# design.net
KiCad netlist of a schematic drawn in Altium Designer
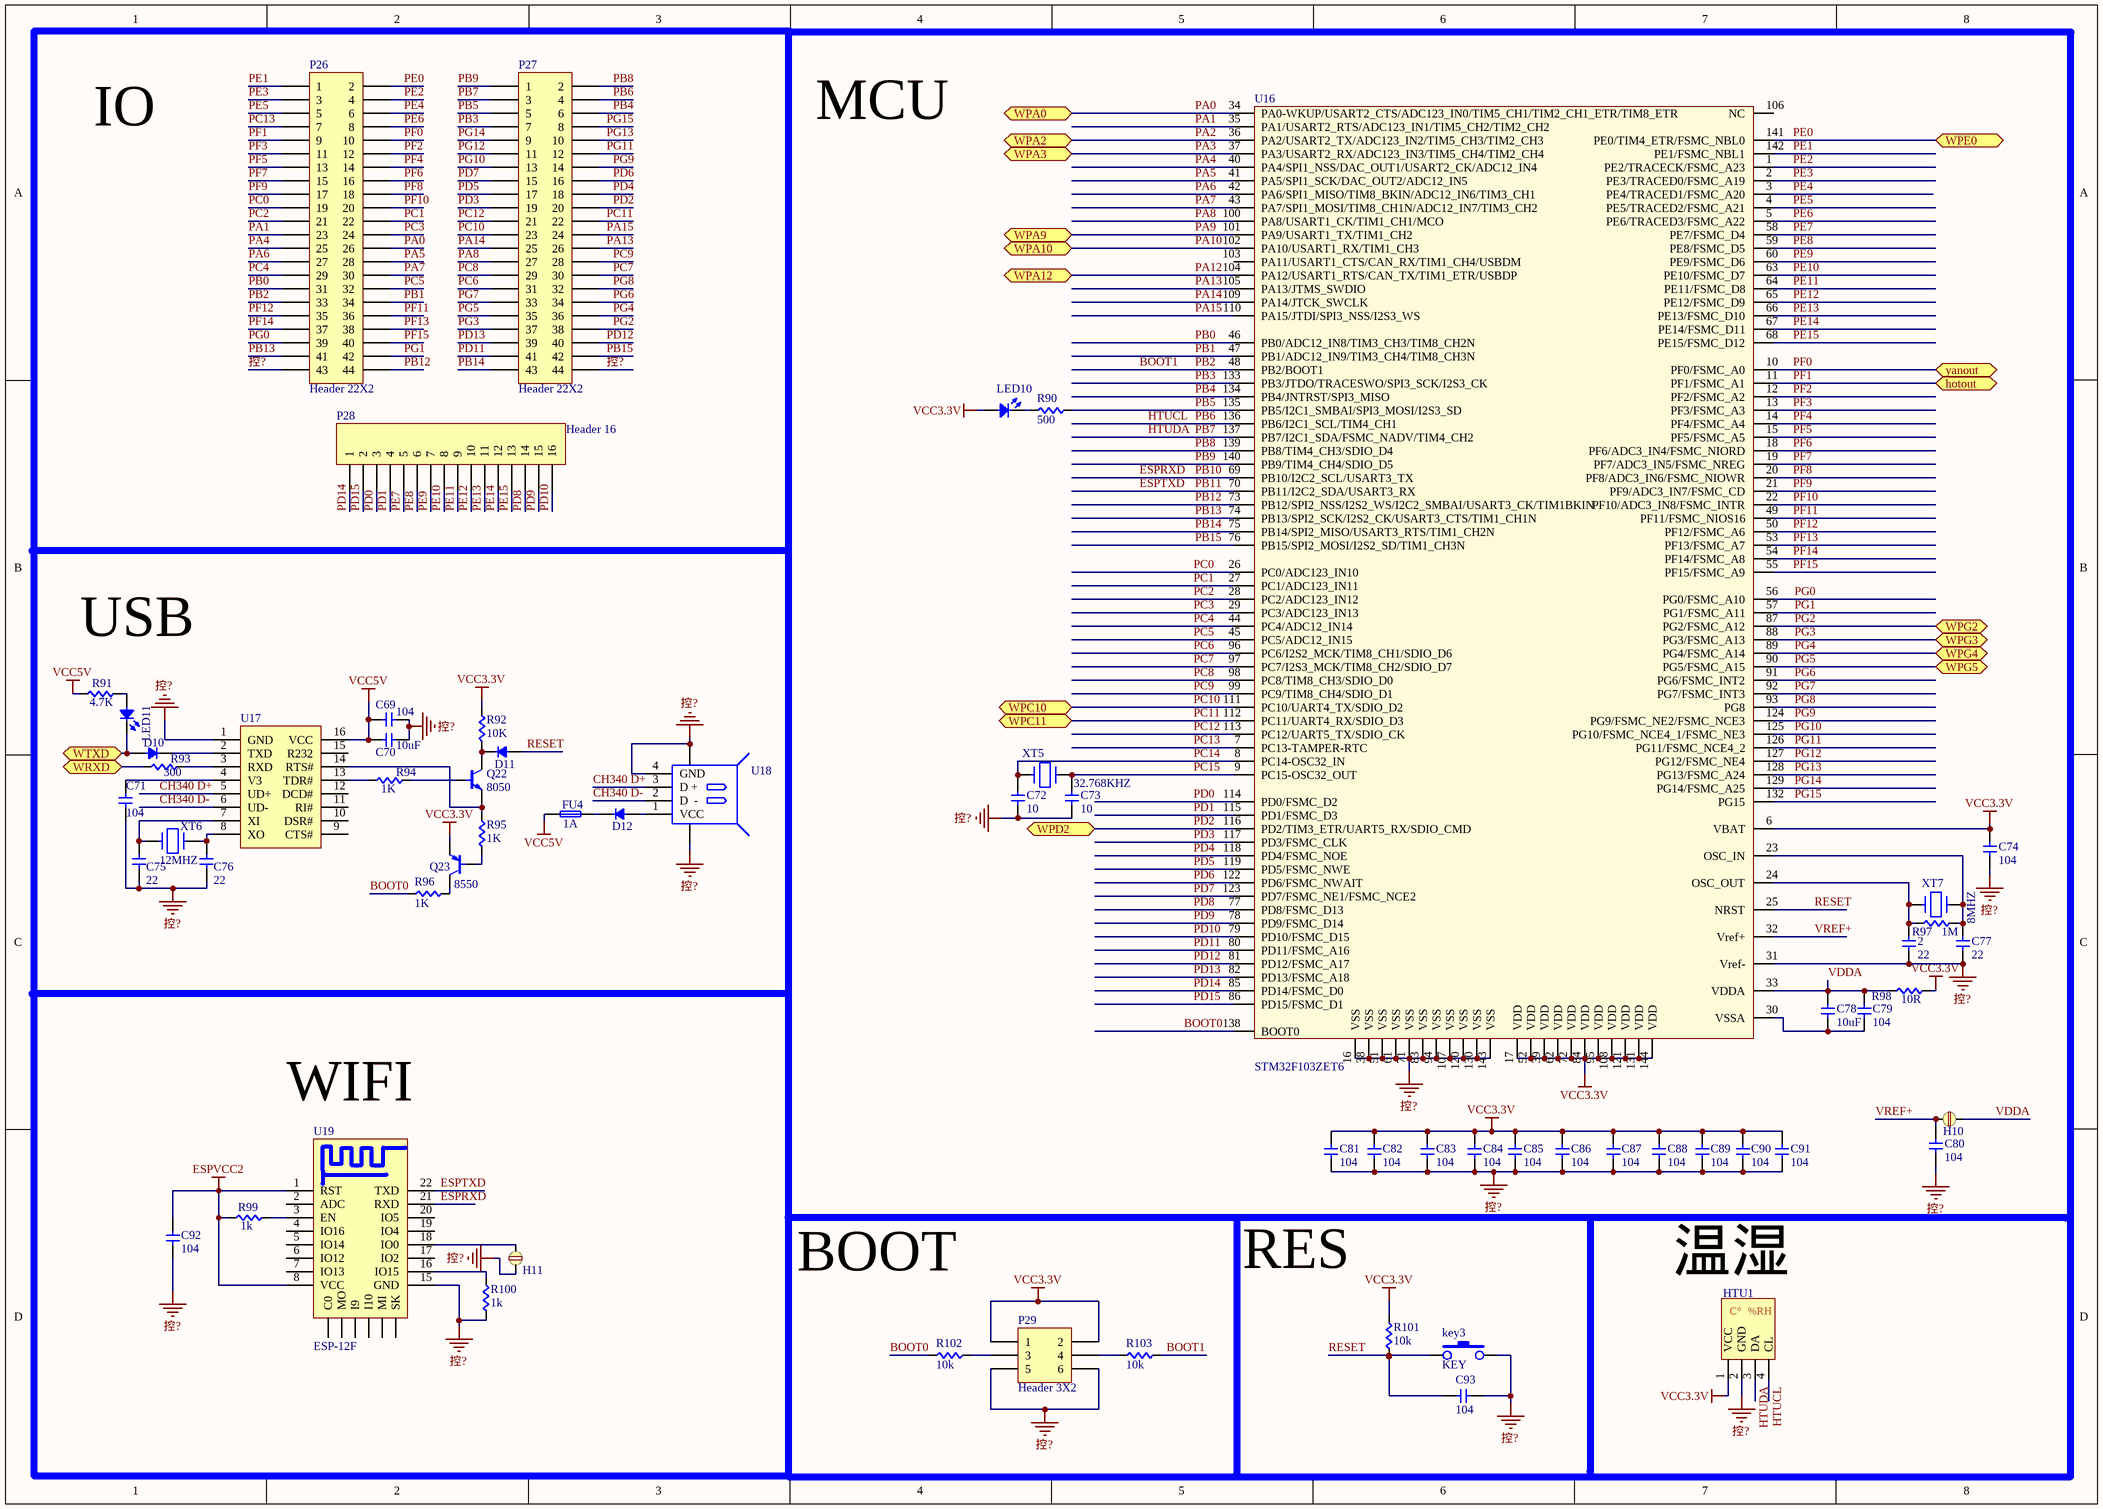
[diagram p0: 小车主板原理图.SchDoc]

(export (version "E")
  (design (tool "Eeschema 10.0.6"))
  (components
    (comp (ref "2") (value "22") (footprint "0805C") (libsource (lib "史福祥库") (part "C")))
    (comp (ref "C69") (value "104") (footprint "0805C") (libsource (lib "史福祥库") (part "C")))
    (comp (ref "C70") (value "10uF") (footprint "0805C") (libsource (lib "史福祥库") (part "C")))
    (comp (ref "C71") (value "104") (footprint "0805C") (libsource (lib "史福祥库") (part "C")))
    (comp (ref "C72") (value "10") (footprint "0805C") (libsource (lib "史福祥库") (part "C")))
    (comp (ref "C73") (value "10") (footprint "0805C") (libsource (lib "史福祥库") (part "C")))
    (comp (ref "C74") (value "104") (footprint "0805C") (libsource (lib "史福祥库") (part "C")))
    (comp (ref "C75") (value "22") (footprint "0805C") (libsource (lib "史福祥库") (part "C")))
    (comp (ref "C76") (value "22") (footprint "0805C") (libsource (lib "史福祥库") (part "C")))
    (comp (ref "C77") (value "22") (footprint "0805C") (libsource (lib "史福祥库") (part "C")))
    (comp (ref "C78") (value "10uF") (footprint "0805C") (libsource (lib "史福祥库") (part "C")))
    (comp (ref "C79") (value "104") (footprint "0805C") (libsource (lib "史福祥库") (part "C")))
    (comp (ref "C80") (value "104") (footprint "0805C") (libsource (lib "史福祥库") (part "C")))
    (comp (ref "C81") (value "104") (footprint "0805C") (libsource (lib "史福祥库") (part "C")))
    (comp (ref "C82") (value "104") (footprint "0805C") (libsource (lib "史福祥库") (part "C")))
    (comp (ref "C83") (value "104") (footprint "0805C") (libsource (lib "史福祥库") (part "C")))
    (comp (ref "C84") (value "104") (footprint "0805C") (libsource (lib "史福祥库") (part "C")))
    (comp (ref "C85") (value "104") (footprint "0805C") (libsource (lib "史福祥库") (part "C")))
    (comp (ref "C86") (value "104") (footprint "0805C") (libsource (lib "史福祥库") (part "C")))
    (comp (ref "C87") (value "104") (footprint "0805C") (libsource (lib "史福祥库") (part "C")))
    (comp (ref "C88") (value "104") (footprint "0805C") (libsource (lib "史福祥库") (part "C")))
    (comp (ref "C89") (value "104") (footprint "0805C") (libsource (lib "史福祥库") (part "C")))
    (comp (ref "C90") (value "104") (footprint "0805C") (libsource (lib "史福祥库") (part "C")))
    (comp (ref "C91") (value "104") (footprint "0805C") (libsource (lib "史福祥库") (part "C")))
    (comp (ref "C92") (value "104") (footprint "0805C") (libsource (lib "史福祥库") (part "C")))
    (comp (ref "C93") (value "104") (footprint "0805C") (libsource (lib "史福祥库") (part "C")))
    (comp (ref "D10")
      (value "D")
      (footprint "1206D")
      (fields (field (name "PUBLISHER") "Altium Limited"))
      (libsource (lib "史福祥库") (part "D"))
    )
    (comp (ref "D11")
      (value "D")
      (footprint "1206D")
      (fields (field (name "PUBLISHER") "Altium Limited"))
      (libsource (lib "史福祥库") (part "D"))
    )
    (comp (ref "D12")
      (value "D")
      (footprint "DO-214-M7-  4007贴片")
      (fields (field (name "PUBLISHER") "Altium Limited"))
      (libsource (lib "史福祥库") (part "D"))
    )
    (comp (ref "FU4") (value "1A") (footprint "1206") (libsource (lib "史福祥库") (part "FUSE")))
    (comp (ref "H10") (value "2脚") (footprint "2P") (libsource (lib "") (part "2脚_1")))
    (comp (ref "H11") (value "2脚") (footprint "2P") (libsource (lib "史福祥库") (part "2脚")))
    (comp (ref "HTU1") (value "HTU21D") (footprint "HDR1X4H") (libsource (lib "史福祥库") (part "HTU21D")))
    (comp (ref "key3") (value "KEY") (footprint "AN12") (libsource (lib "史福祥库") (part "KEY")))
    (comp (ref "LED10")
      (value "LED")
      (footprint "0805D")
      (fields (field (name "PUBLISHER") "Altium Limited"))
      (libsource (lib "史福祥库") (part "LED"))
    )
    (comp (ref "LED11")
      (value "LED")
      (footprint "0805D")
      (fields (field (name "PUBLISHER") "Altium Limited"))
      (libsource (lib "史福祥库") (part "LED"))
    )
    (comp (ref "P26")
      (value "Header 22X2")
      (footprint "HDR2X22")
      (description "Header, 22-Pin, Dual row")
      (fields (field (name "PUBLISHER") "Altium Limited"))
      (libsource (lib "Miscellaneous Connectors") (part "Header 22X2"))
    )
    (comp (ref "P27")
      (value "Header 22X2")
      (footprint "HDR2X22")
      (description "Header, 22-Pin, Dual row")
      (fields (field (name "PUBLISHER") "Altium Limited"))
      (libsource (lib "Miscellaneous Connectors") (part "Header 22X2"))
    )
    (comp (ref "P28")
      (value "Header 16")
      (footprint "HDR1X16")
      (description "Header, 16-Pin")
      (fields (field (name "PUBLISHER") "Altium Limited"))
      (libsource (lib "Miscellaneous Connectors") (part "Header 16"))
    )
    (comp (ref "P29")
      (value "Header 3X2")
      (footprint "HDR2X3")
      (description "Header, 3-Pin, Dual row")
      (fields (field (name "PUBLISHER") "Altium Limited"))
      (libsource (lib "Miscellaneous Connectors") (part "Header 3X2"))
    )
    (comp (ref "Q22") (value "8050") (footprint "SOT-23") (libsource (lib "史福祥库") (part "NPN")))
    (comp (ref "Q23") (value "8550") (footprint "SOT-23") (libsource (lib "史福祥库") (part "PNP")))
    (comp (ref "R90") (value "500") (footprint "0805") (libsource (lib "史福祥库") (part "Res")))
    (comp (ref "R91") (value "4.7K") (footprint "0805") (libsource (lib "史福祥库") (part "Res")))
    (comp (ref "R92") (value "10K") (footprint "0805") (libsource (lib "史福祥库") (part "Res")))
    (comp (ref "R93") (value "300") (footprint "0805") (libsource (lib "史福祥库") (part "Res")))
    (comp (ref "R94") (value "1K") (footprint "0805") (libsource (lib "史福祥库") (part "Res")))
    (comp (ref "R95") (value "1K") (footprint "0805") (libsource (lib "史福祥库") (part "Res")))
    (comp (ref "R96") (value "1K") (footprint "0805") (libsource (lib "史福祥库") (part "Res")))
    (comp (ref "R97") (value "1M") (footprint "0805") (libsource (lib "史福祥库") (part "Res")))
    (comp (ref "R98") (value "10R") (footprint "0805") (libsource (lib "史福祥库") (part "Res")))
    (comp (ref "R99") (value "1k") (footprint "0805") (libsource (lib "史福祥库") (part "Res")))
    (comp (ref "R100") (value "1k") (footprint "0805") (libsource (lib "史福祥库") (part "Res")))
    (comp (ref "R101") (value "10k") (footprint "0805") (libsource (lib "史福祥库") (part "Res")))
    (comp (ref "R102") (value "10k") (footprint "0805") (libsource (lib "史福祥库") (part "Res")))
    (comp (ref "R103") (value "10k") (footprint "0805") (libsource (lib "史福祥库") (part "Res")))
    (comp (ref "U16")
      (value "STM32F103ZET6")
      (footprint "TQFP144")
      (libsource (lib "史福祥库") (part "STM32F103ZET6"))
    )
    (comp (ref "U17") (value "CH340G") (footprint "SOP-16") (libsource (lib "史福祥库") (part "CH340G")))
    (comp (ref "U18") (value "USB A") (footprint "USB A 公") (libsource (lib "史福祥库") (part "USB A")))
    (comp (ref "U19") (value "ESP-12F") (footprint "ESP-12F") (libsource (lib "史福祥库") (part "ESP-12F")))
    (comp (ref "XT5") (value "32.768KHZ") (footprint "XTAL-T") (libsource (lib "史福祥库") (part "XTAL")))
    (comp (ref "XT6") (value "12MHZ") (footprint "XTAL-T") (libsource (lib "史福祥库") (part "XTAL")))
    (comp (ref "XT7") (value "8MHZ") (footprint "XTAL-T") (libsource (lib "史福祥库") (part "XTAL")))
  )
  (nets
    (net (code "1") (name "/BOOT0") (class "Default")
      (node (ref "R102") (pin "2") (pinfunction "2_2") (pintype "passive"))
      (node (ref "R96") (pin "1") (pinfunction "1_1") (pintype "passive"))
      (node (ref "U16") (pin "138") (pinfunction "BOOT0_138") (pintype "passive"))
    )
    (net (code "2") (name "/BOOT1") (class "Default")
      (node (ref "P26") (pin "33") (pinfunction "33_33") (pintype "passive"))
      (node (ref "R103") (pin "1") (pinfunction "1_1") (pintype "passive"))
      (node (ref "U16") (pin "48") (pinfunction "PB2/BOOT1_48") (pintype "passive"))
    )
    (net (code "3") (name "/CH340 D+") (class "Default")
      (node (ref "U17") (pin "5") (pinfunction "UD+_5") (pintype "passive"))
      (node (ref "U18") (pin "3") (pinfunction "D_+_3") (pintype "passive"))
    )
    (net (code "4") (name "/CH340 D-") (class "Default")
      (node (ref "U17") (pin "6") (pinfunction "UD-_6") (pintype "passive"))
      (node (ref "U18") (pin "2") (pinfunction "D__-_2") (pintype "passive"))
    )
    (net (code "5") (name "/ESPRXD") (class "Default")
      (node (ref "U16") (pin "69") (pinfunction "PB10/I2C2_SCL/USART3_TX_69") (pintype "passive"))
      (node (ref "U19") (pin "21") (pinfunction "RXD_21") (pintype "passive"))
    )
    (net (code "6") (name "/ESPTXD") (class "Default")
      (node (ref "U16") (pin "70") (pinfunction "PB11/I2C2_SDA/USART3_RX_70") (pintype "passive"))
      (node (ref "U19") (pin "22") (pinfunction "TXD_22") (pintype "passive"))
    )
    (net (code "7") (name "/HTUCL") (class "Default")
      (node (ref "HTU1") (pin "4") (pinfunction "CL_4") (pintype "tri_state"))
      (node (ref "P27") (pin "4") (pinfunction "4_4") (pintype "passive"))
      (node (ref "U16") (pin "136") (pinfunction "PB6/I2C1_SCL/TIM4_CH1_136") (pintype "passive"))
    )
    (net (code "8") (name "/HTUDA") (class "Default")
      (node (ref "HTU1") (pin "3") (pinfunction "DA_3") (pintype "tri_state"))
      (node (ref "P27") (pin "3") (pinfunction "3_3") (pintype "passive"))
      (node (ref "U16") (pin "137") (pinfunction "PB7/I2C1_SDA/FSMC_NADV/TIM4_CH2_137") (pintype "passive"))
    )
    (net (code "9") (name "/PA0") (class "Default")
      (node (ref "P26") (pin "26") (pinfunction "26_26") (pintype "passive"))
      (node (ref "U16") (pin "34") (pinfunction "PA0-WKUP/USART2_CTS/ADC123_IN0/TIM5_CH1/TIM2_CH1_ETR/TIM8_ETR_34") (pintype "passive"))
    )
    (net (code "10") (name "/PA1") (class "Default")
      (node (ref "P26") (pin "23") (pinfunction "23_23") (pintype "passive"))
      (node (ref "U16") (pin "35") (pinfunction "PA1/USART2_RTS/ADC123_IN1/TIM5_CH2/TIM2_CH2_35") (pintype "passive"))
    )
    (net (code "11") (name "/PA2") (class "Default")
      (node (ref "U16") (pin "36") (pinfunction "PA2/USART2_TX/ADC123_IN2/TIM5_CH3/TIM2_CH3_36") (pintype "passive"))
    )
    (net (code "12") (name "/PA3") (class "Default")
      (node (ref "U16") (pin "37") (pinfunction "PA3/USART2_RX/ADC123_IN3/TIM5_CH4/TIM2_CH4_37") (pintype "passive"))
    )
    (net (code "13") (name "/PA4") (class "Default")
      (node (ref "P26") (pin "25") (pinfunction "25_25") (pintype "passive"))
      (node (ref "U16") (pin "40") (pinfunction "PA4/SPI1_NSS/DAC_OUT1/USART2_CK/ADC12_IN4_40") (pintype "passive"))
    )
    (net (code "14") (name "/PA5") (class "Default")
      (node (ref "P26") (pin "28") (pinfunction "28_28") (pintype "passive"))
      (node (ref "U16") (pin "41") (pinfunction "PA5/SPI1_SCK/DAC_OUT2/ADC12_IN5_41") (pintype "passive"))
    )
    (net (code "15") (name "/PA6") (class "Default")
      (node (ref "P26") (pin "27") (pinfunction "27_27") (pintype "passive"))
      (node (ref "U16") (pin "42") (pinfunction "PA6/SPI1_MISO/TIM8_BKIN/ADC12_IN6/TIM3_CH1_42") (pintype "passive"))
    )
    (net (code "16") (name "/PA7") (class "Default")
      (node (ref "P26") (pin "30") (pinfunction "30_30") (pintype "passive"))
      (node (ref "U16") (pin "43") (pinfunction "PA7/SPI1_MOSI/TIM8_CH1N/ADC12_IN7/TIM3_CH2_43") (pintype "passive"))
    )
    (net (code "17") (name "/PA8") (class "Default")
      (node (ref "P27") (pin "27") (pinfunction "27_27") (pintype "passive"))
      (node (ref "U16") (pin "100") (pinfunction "PA8/USART1_CK/TIM1_CH1/MCO_100") (pintype "passive"))
    )
    (net (code "18") (name "/PA9") (class "Default")
      (node (ref "U16") (pin "101") (pinfunction "PA9/USART1_TX/TIM1_CH2_101") (pintype "passive"))
    )
    (net (code "19") (name "/PA10") (class "Default")
      (node (ref "U16") (pin "102") (pinfunction "PA10/USART1_RX/TIM1_CH3_102") (pintype "passive"))
    )
    (net (code "20") (name "/PA12") (class "Default")
      (node (ref "U16") (pin "104") (pinfunction "PA12/USART1_RTS/CAN_TX/TIM1_ETR/USBDP_104") (pintype "passive"))
    )
    (net (code "21") (name "/PA13") (class "Default")
      (node (ref "P27") (pin "26") (pinfunction "26_26") (pintype "passive"))
      (node (ref "U16") (pin "105") (pinfunction "PA13/JTMS_SWDIO_105") (pintype "passive"))
    )
    (net (code "22") (name "/PA14") (class "Default")
      (node (ref "P27") (pin "25") (pinfunction "25_25") (pintype "passive"))
      (node (ref "U16") (pin "109") (pinfunction "PA14/JTCK_SWCLK_109") (pintype "passive"))
    )
    (net (code "23") (name "/PA15") (class "Default")
      (node (ref "P27") (pin "24") (pinfunction "24_24") (pintype "passive"))
      (node (ref "U16") (pin "110") (pinfunction "PA15/JTDI/SPI3_NSS/I2S3_WS_110") (pintype "passive"))
    )
    (net (code "24") (name "/PB0") (class "Default")
      (node (ref "P26") (pin "31") (pinfunction "31_31") (pintype "passive"))
      (node (ref "U16") (pin "46") (pinfunction "PB0/ADC12_IN8/TIM3_CH3/TIM8_CH2N_46") (pintype "passive"))
    )
    (net (code "25") (name "/PB1") (class "Default")
      (node (ref "P26") (pin "34") (pinfunction "34_34") (pintype "passive"))
      (node (ref "U16") (pin "47") (pinfunction "PB1/ADC12_IN9/TIM3_CH4/TIM8_CH3N_47") (pintype "passive"))
    )
    (net (code "26") (name "/PB3") (class "Default")
      (node (ref "P27") (pin "7") (pinfunction "7_7") (pintype "passive"))
      (node (ref "U16") (pin "133") (pinfunction "PB3/JTDO/TRACESWO/SPI3_SCK/I2S3_CK_133") (pintype "passive"))
    )
    (net (code "27") (name "/PB4") (class "Default")
      (node (ref "P27") (pin "6") (pinfunction "6_6") (pintype "passive"))
      (node (ref "U16") (pin "134") (pinfunction "PB4/JNTRST/SPI3_MISO_134") (pintype "passive"))
    )
    (net (code "28") (name "/PB5") (class "Default")
      (node (ref "P27") (pin "5") (pinfunction "5_5") (pintype "passive"))
      (node (ref "R90") (pin "2") (pinfunction "2_2") (pintype "passive"))
      (node (ref "U16") (pin "135") (pinfunction "PB5/I2C1_SMBAI/SPI3_MOSI/I2S3_SD_135") (pintype "passive"))
    )
    (net (code "29") (name "/PB8") (class "Default")
      (node (ref "P27") (pin "2") (pinfunction "2_2") (pintype "passive"))
      (node (ref "U16") (pin "139") (pinfunction "PB8/TIM4_CH3/SDIO_D4_139") (pintype "passive"))
    )
    (net (code "30") (name "/PB9") (class "Default")
      (node (ref "P27") (pin "1") (pinfunction "1_1") (pintype "passive"))
      (node (ref "U16") (pin "140") (pinfunction "PB9/TIM4_CH4/SDIO_D5_140") (pintype "passive"))
    )
    (net (code "31") (name "/PB12") (class "Default")
      (node (ref "P26") (pin "44") (pinfunction "44_44") (pintype "passive"))
      (node (ref "U16") (pin "73") (pinfunction "PB12/SPI2_NSS/I2S2_WS/I2C2_SMBAI/USART3_CK/TIM1BKIN_73") (pintype "passive"))
    )
    (net (code "32") (name "/PB13") (class "Default")
      (node (ref "P26") (pin "41") (pinfunction "41_41") (pintype "passive"))
      (node (ref "U16") (pin "74") (pinfunction "PB13/SPI2_SCK/I2S2_CK/USART3_CTS/TIM1_CH1N_74") (pintype "passive"))
    )
    (net (code "33") (name "/PB14") (class "Default")
      (node (ref "P27") (pin "43") (pinfunction "43_43") (pintype "passive"))
      (node (ref "U16") (pin "75") (pinfunction "PB14/SPI2_MISO/USART3_RTS/TIM1_CH2N_75") (pintype "passive"))
    )
    (net (code "34") (name "/PB15") (class "Default")
      (node (ref "P27") (pin "42") (pinfunction "42_42") (pintype "passive"))
      (node (ref "U16") (pin "76") (pinfunction "PB15/SPI2_MOSI/I2S2_SD/TIM1_CH3N_76") (pintype "passive"))
    )
    (net (code "35") (name "/PC0") (class "Default")
      (node (ref "P26") (pin "19") (pinfunction "19_19") (pintype "passive"))
      (node (ref "U16") (pin "26") (pinfunction "PC0/ADC123_IN10_26") (pintype "passive"))
    )
    (net (code "36") (name "/PC1") (class "Default")
      (node (ref "P26") (pin "22") (pinfunction "22_22") (pintype "passive"))
      (node (ref "U16") (pin "27") (pinfunction "PC1/ADC123_IN11_27") (pintype "passive"))
    )
    (net (code "37") (name "/PC2") (class "Default")
      (node (ref "P26") (pin "21") (pinfunction "21_21") (pintype "passive"))
      (node (ref "U16") (pin "28") (pinfunction "PC2/ADC123_IN12_28") (pintype "passive"))
    )
    (net (code "38") (name "/PC3") (class "Default")
      (node (ref "P26") (pin "24") (pinfunction "24_24") (pintype "passive"))
      (node (ref "U16") (pin "29") (pinfunction "PC3/ADC123_IN13_29") (pintype "passive"))
    )
    (net (code "39") (name "/PC4") (class "Default")
      (node (ref "P26") (pin "29") (pinfunction "29_29") (pintype "passive"))
      (node (ref "U16") (pin "44") (pinfunction "PC4/ADC12_IN14_44") (pintype "passive"))
    )
    (net (code "40") (name "/PC5") (class "Default")
      (node (ref "P26") (pin "32") (pinfunction "32_32") (pintype "passive"))
      (node (ref "U16") (pin "45") (pinfunction "PC5/ADC12_IN15_45") (pintype "passive"))
    )
    (net (code "41") (name "/PC6") (class "Default")
      (node (ref "P27") (pin "31") (pinfunction "31_31") (pintype "passive"))
      (node (ref "U16") (pin "96") (pinfunction "PC6/I2S2_MCK/TIM8_CH1/SDIO_D6_96") (pintype "passive"))
    )
    (net (code "42") (name "/PC7") (class "Default")
      (node (ref "P27") (pin "30") (pinfunction "30_30") (pintype "passive"))
      (node (ref "U16") (pin "97") (pinfunction "PC7/I2S3_MCK/TIM8_CH2/SDIO_D7_97") (pintype "passive"))
    )
    (net (code "43") (name "/PC8") (class "Default")
      (node (ref "P27") (pin "29") (pinfunction "29_29") (pintype "passive"))
      (node (ref "U16") (pin "98") (pinfunction "PC8/TIM8_CH3/SDIO_D0_98") (pintype "passive"))
    )
    (net (code "44") (name "/PC9") (class "Default")
      (node (ref "P27") (pin "28") (pinfunction "28_28") (pintype "passive"))
      (node (ref "U16") (pin "99") (pinfunction "PC9/TIM8_CH4/SDIO_D1_99") (pintype "passive"))
    )
    (net (code "45") (name "/PC10") (class "Default")
      (node (ref "P27") (pin "23") (pinfunction "23_23") (pintype "passive"))
      (node (ref "U16") (pin "111") (pinfunction "PC10/UART4_TX/SDIO_D2_111") (pintype "passive"))
    )
    (net (code "46") (name "/PC11") (class "Default")
      (node (ref "P27") (pin "22") (pinfunction "22_22") (pintype "passive"))
      (node (ref "U16") (pin "112") (pinfunction "PC11/UART4_RX/SDIO_D3_112") (pintype "passive"))
    )
    (net (code "47") (name "/PC12") (class "Default")
      (node (ref "P27") (pin "21") (pinfunction "21_21") (pintype "passive"))
      (node (ref "U16") (pin "113") (pinfunction "PC12/UART5_TX/SDIO_CK_113") (pintype "passive"))
    )
    (net (code "48") (name "/PC13") (class "Default")
      (node (ref "P26") (pin "7") (pinfunction "7_7") (pintype "passive"))
      (node (ref "U16") (pin "7") (pinfunction "PC13-TAMPER-RTC_7") (pintype "passive"))
    )
    (net (code "49") (name "/PC14") (class "Default")
      (node (ref "C72") (pin "2") (pinfunction "2_2") (pintype "passive"))
      (node (ref "U16") (pin "8") (pinfunction "PC14-OSC32_IN_8") (pintype "passive"))
      (node (ref "XT5") (pin "1") (pinfunction "1_1") (pintype "passive"))
    )
    (net (code "50") (name "/PC15") (class "Default")
      (node (ref "C73") (pin "2") (pinfunction "2_2") (pintype "passive"))
      (node (ref "U16") (pin "9") (pinfunction "PC15-OSC32_OUT_9") (pintype "passive"))
      (node (ref "XT5") (pin "2") (pinfunction "2_2") (pintype "passive"))
    )
    (net (code "51") (name "/PD0") (class "Default")
      (node (ref "P28") (pin "3") (pinfunction "3_3") (pintype "passive"))
      (node (ref "U16") (pin "114") (pinfunction "PD0/FSMC_D2_114") (pintype "passive"))
    )
    (net (code "52") (name "/PD1") (class "Default")
      (node (ref "P28") (pin "4") (pinfunction "4_4") (pintype "passive"))
      (node (ref "U16") (pin "115") (pinfunction "PD1/FSMC_D3_115") (pintype "passive"))
    )
    (net (code "53") (name "/PD2") (class "Default")
      (node (ref "P27") (pin "20") (pinfunction "20_20") (pintype "passive"))
      (node (ref "U16") (pin "116") (pinfunction "PD2/TIM3_ETR/UART5_RX/SDIO_CMD_116") (pintype "passive"))
    )
    (net (code "54") (name "/PD3") (class "Default")
      (node (ref "P27") (pin "19") (pinfunction "19_19") (pintype "passive"))
      (node (ref "U16") (pin "117") (pinfunction "PD3/FSMC_CLK_117") (pintype "passive"))
    )
    (net (code "55") (name "/PD4") (class "Default")
      (node (ref "P27") (pin "18") (pinfunction "18_18") (pintype "passive"))
      (node (ref "U16") (pin "118") (pinfunction "PD4/FSMC_NOE_118") (pintype "passive"))
    )
    (net (code "56") (name "/PD5") (class "Default")
      (node (ref "P27") (pin "17") (pinfunction "17_17") (pintype "passive"))
      (node (ref "U16") (pin "119") (pinfunction "PD5/FSMC_NWE_119") (pintype "passive"))
    )
    (net (code "57") (name "/PD6") (class "Default")
      (node (ref "P27") (pin "16") (pinfunction "16_16") (pintype "passive"))
      (node (ref "U16") (pin "122") (pinfunction "PD6/FSMC_NWAIT_122") (pintype "passive"))
    )
    (net (code "58") (name "/PD7") (class "Default")
      (node (ref "P27") (pin "15") (pinfunction "15_15") (pintype "passive"))
      (node (ref "U16") (pin "123") (pinfunction "PD7/FSMC_NE1/FSMC_NCE2_123") (pintype "passive"))
    )
    (net (code "59") (name "/PD8") (class "Default")
      (node (ref "P28") (pin "14") (pinfunction "14_14") (pintype "passive"))
      (node (ref "U16") (pin "77") (pinfunction "PD8/FSMC_D13_77") (pintype "passive"))
    )
    (net (code "60") (name "/PD9") (class "Default")
      (node (ref "P28") (pin "15") (pinfunction "15_15") (pintype "passive"))
      (node (ref "U16") (pin "78") (pinfunction "PD9/FSMC_D14_78") (pintype "passive"))
    )
    (net (code "61") (name "/PD10") (class "Default")
      (node (ref "P28") (pin "16") (pinfunction "16_16") (pintype "passive"))
      (node (ref "U16") (pin "79") (pinfunction "PD10/FSMC_D15_79") (pintype "passive"))
    )
    (net (code "62") (name "/PD11") (class "Default")
      (node (ref "P27") (pin "41") (pinfunction "41_41") (pintype "passive"))
      (node (ref "U16") (pin "80") (pinfunction "PD11/FSMC_A16_80") (pintype "passive"))
    )
    (net (code "63") (name "/PD12") (class "Default")
      (node (ref "P27") (pin "40") (pinfunction "40_40") (pintype "passive"))
      (node (ref "U16") (pin "81") (pinfunction "PD12/FSMC_A17_81") (pintype "passive"))
    )
    (net (code "64") (name "/PD13") (class "Default")
      (node (ref "P27") (pin "39") (pinfunction "39_39") (pintype "passive"))
      (node (ref "U16") (pin "82") (pinfunction "PD13/FSMC_A18_82") (pintype "passive"))
    )
    (net (code "65") (name "/PD14") (class "Default")
      (node (ref "P28") (pin "1") (pinfunction "1_1") (pintype "passive"))
      (node (ref "U16") (pin "85") (pinfunction "PD14/FSMC_D0_85") (pintype "passive"))
    )
    (net (code "66") (name "/PD15") (class "Default")
      (node (ref "P28") (pin "2") (pinfunction "2_2") (pintype "passive"))
      (node (ref "U16") (pin "86") (pinfunction "PD15/FSMC_D1_86") (pintype "passive"))
    )
    (net (code "67") (name "/PE0") (class "Default")
      (node (ref "P26") (pin "2") (pinfunction "2_2") (pintype "passive"))
      (node (ref "U16") (pin "141") (pinfunction "PE0/TIM4_ETR/FSMC_NBL0_141") (pintype "passive"))
    )
    (net (code "68") (name "/PE1") (class "Default")
      (node (ref "P26") (pin "1") (pinfunction "1_1") (pintype "passive"))
      (node (ref "U16") (pin "142") (pinfunction "PE1/FSMC_NBL1_142") (pintype "passive"))
    )
    (net (code "69") (name "/PE2") (class "Default")
      (node (ref "P26") (pin "4") (pinfunction "4_4") (pintype "passive"))
      (node (ref "U16") (pin "1") (pinfunction "PE2/TRACECK/FSMC_A23_1") (pintype "passive"))
    )
    (net (code "70") (name "/PE3") (class "Default")
      (node (ref "P26") (pin "3") (pinfunction "3_3") (pintype "passive"))
      (node (ref "U16") (pin "2") (pinfunction "PE3/TRACED0/FSMC_A19_2") (pintype "passive"))
    )
    (net (code "71") (name "/PE4") (class "Default")
      (node (ref "P26") (pin "6") (pinfunction "6_6") (pintype "passive"))
      (node (ref "U16") (pin "3") (pinfunction "PE4/TRACED1/FSMC_A20_3") (pintype "passive"))
    )
    (net (code "72") (name "/PE5") (class "Default")
      (node (ref "P26") (pin "5") (pinfunction "5_5") (pintype "passive"))
      (node (ref "U16") (pin "4") (pinfunction "PE5/TRACED2/FSMC_A21_4") (pintype "passive"))
    )
    (net (code "73") (name "/PE6") (class "Default")
      (node (ref "P26") (pin "8") (pinfunction "8_8") (pintype "passive"))
      (node (ref "U16") (pin "5") (pinfunction "PE6/TRACED3/FSMC_A22_5") (pintype "passive"))
    )
    (net (code "74") (name "/PE7") (class "Default")
      (node (ref "P28") (pin "5") (pinfunction "5_5") (pintype "passive"))
      (node (ref "U16") (pin "58") (pinfunction "PE7/FSMC_D4_58") (pintype "passive"))
    )
    (net (code "75") (name "/PE8") (class "Default")
      (node (ref "P28") (pin "6") (pinfunction "6_6") (pintype "passive"))
      (node (ref "U16") (pin "59") (pinfunction "PE8/FSMC_D5_59") (pintype "passive"))
    )
    (net (code "76") (name "/PE9") (class "Default")
      (node (ref "P28") (pin "7") (pinfunction "7_7") (pintype "passive"))
      (node (ref "U16") (pin "60") (pinfunction "PE9/FSMC_D6_60") (pintype "passive"))
    )
    (net (code "77") (name "/PE10") (class "Default")
      (node (ref "P28") (pin "8") (pinfunction "8_8") (pintype "passive"))
      (node (ref "U16") (pin "63") (pinfunction "PE10/FSMC_D7_63") (pintype "passive"))
    )
    (net (code "78") (name "/PE11") (class "Default")
      (node (ref "P28") (pin "9") (pinfunction "9_9") (pintype "passive"))
      (node (ref "U16") (pin "64") (pinfunction "PE11/FSMC_D8_64") (pintype "passive"))
    )
    (net (code "79") (name "/PE12") (class "Default")
      (node (ref "P28") (pin "10") (pinfunction "10_10") (pintype "passive"))
      (node (ref "U16") (pin "65") (pinfunction "PE12/FSMC_D9_65") (pintype "passive"))
    )
    (net (code "80") (name "/PE13") (class "Default")
      (node (ref "P28") (pin "11") (pinfunction "11_11") (pintype "passive"))
      (node (ref "U16") (pin "66") (pinfunction "PE13/FSMC_D10_66") (pintype "passive"))
    )
    (net (code "81") (name "/PE14") (class "Default")
      (node (ref "P28") (pin "12") (pinfunction "12_12") (pintype "passive"))
      (node (ref "U16") (pin "67") (pinfunction "PE14/FSMC_D11_67") (pintype "passive"))
    )
    (net (code "82") (name "/PE15") (class "Default")
      (node (ref "P28") (pin "13") (pinfunction "13_13") (pintype "passive"))
      (node (ref "U16") (pin "68") (pinfunction "PE15/FSMC_D12_68") (pintype "passive"))
    )
    (net (code "83") (name "/PF0") (class "Default")
      (node (ref "P26") (pin "10") (pinfunction "10_10") (pintype "passive"))
      (node (ref "U16") (pin "10") (pinfunction "PF0/FSMC_A0_10") (pintype "passive"))
    )
    (net (code "84") (name "/PF1") (class "Default")
      (node (ref "P26") (pin "9") (pinfunction "9_9") (pintype "passive"))
      (node (ref "U16") (pin "11") (pinfunction "PF1/FSMC_A1_11") (pintype "passive"))
    )
    (net (code "85") (name "/PF2") (class "Default")
      (node (ref "P26") (pin "12") (pinfunction "12_12") (pintype "passive"))
      (node (ref "U16") (pin "12") (pinfunction "PF2/FSMC_A2_12") (pintype "passive"))
    )
    (net (code "86") (name "/PF3") (class "Default")
      (node (ref "P26") (pin "11") (pinfunction "11_11") (pintype "passive"))
      (node (ref "U16") (pin "13") (pinfunction "PF3/FSMC_A3_13") (pintype "passive"))
    )
    (net (code "87") (name "/PF4") (class "Default")
      (node (ref "P26") (pin "14") (pinfunction "14_14") (pintype "passive"))
      (node (ref "U16") (pin "14") (pinfunction "PF4/FSMC_A4_14") (pintype "passive"))
    )
    (net (code "88") (name "/PF5") (class "Default")
      (node (ref "P26") (pin "13") (pinfunction "13_13") (pintype "passive"))
      (node (ref "U16") (pin "15") (pinfunction "PF5/FSMC_A5_15") (pintype "passive"))
    )
    (net (code "89") (name "/PF6") (class "Default")
      (node (ref "P26") (pin "16") (pinfunction "16_16") (pintype "passive"))
      (node (ref "U16") (pin "18") (pinfunction "PF6/ADC3_IN4/FSMC_NIORD_18") (pintype "passive"))
    )
    (net (code "90") (name "/PF7") (class "Default")
      (node (ref "P26") (pin "15") (pinfunction "15_15") (pintype "passive"))
      (node (ref "U16") (pin "19") (pinfunction "PF7/ADC3_IN5/FSMC_NREG_19") (pintype "passive"))
    )
    (net (code "91") (name "/PF8") (class "Default")
      (node (ref "P26") (pin "18") (pinfunction "18_18") (pintype "passive"))
      (node (ref "U16") (pin "20") (pinfunction "PF8/ADC3_IN6/FSMC_NIOWR_20") (pintype "passive"))
    )
    (net (code "92") (name "/PF9") (class "Default")
      (node (ref "P26") (pin "17") (pinfunction "17_17") (pintype "passive"))
      (node (ref "U16") (pin "21") (pinfunction "PF9/ADC3_IN7/FSMC_CD_21") (pintype "passive"))
    )
    (net (code "93") (name "/PF10") (class "Default")
      (node (ref "P26") (pin "20") (pinfunction "20_20") (pintype "passive"))
      (node (ref "U16") (pin "22") (pinfunction "PF10/ADC3_IN8/FSMC_INTR_22") (pintype "passive"))
    )
    (net (code "94") (name "/PF11") (class "Default")
      (node (ref "P26") (pin "36") (pinfunction "36_36") (pintype "passive"))
      (node (ref "U16") (pin "49") (pinfunction "PF11/FSMC_NIOS16_49") (pintype "passive"))
    )
    (net (code "95") (name "/PF12") (class "Default")
      (node (ref "P26") (pin "35") (pinfunction "35_35") (pintype "passive"))
      (node (ref "U16") (pin "50") (pinfunction "PF12/FSMC_A6_50") (pintype "passive"))
    )
    (net (code "96") (name "/PF13") (class "Default")
      (node (ref "P26") (pin "38") (pinfunction "38_38") (pintype "passive"))
      (node (ref "U16") (pin "53") (pinfunction "PF13/FSMC_A7_53") (pintype "passive"))
    )
    (net (code "97") (name "/PF14") (class "Default")
      (node (ref "P26") (pin "37") (pinfunction "37_37") (pintype "passive"))
      (node (ref "U16") (pin "54") (pinfunction "PF14/FSMC_A8_54") (pintype "passive"))
    )
    (net (code "98") (name "/PF15") (class "Default")
      (node (ref "P26") (pin "40") (pinfunction "40_40") (pintype "passive"))
      (node (ref "U16") (pin "55") (pinfunction "PF15/FSMC_A9_55") (pintype "passive"))
    )
    (net (code "99") (name "/PG0") (class "Default")
      (node (ref "P26") (pin "39") (pinfunction "39_39") (pintype "passive"))
      (node (ref "U16") (pin "56") (pinfunction "PG0/FSMC_A10_56") (pintype "passive"))
    )
    (net (code "100") (name "/PG1") (class "Default")
      (node (ref "P26") (pin "42") (pinfunction "42_42") (pintype "passive"))
      (node (ref "U16") (pin "57") (pinfunction "PG1/FSMC_A11_57") (pintype "passive"))
    )
    (net (code "101") (name "/PG2") (class "Default")
      (node (ref "P27") (pin "38") (pinfunction "38_38") (pintype "passive"))
      (node (ref "U16") (pin "87") (pinfunction "PG2/FSMC_A12_87") (pintype "passive"))
    )
    (net (code "102") (name "/PG3") (class "Default")
      (node (ref "P27") (pin "37") (pinfunction "37_37") (pintype "passive"))
      (node (ref "U16") (pin "88") (pinfunction "PG3/FSMC_A13_88") (pintype "passive"))
    )
    (net (code "103") (name "/PG4") (class "Default")
      (node (ref "P27") (pin "36") (pinfunction "36_36") (pintype "passive"))
      (node (ref "U16") (pin "89") (pinfunction "PG4/FSMC_A14_89") (pintype "passive"))
    )
    (net (code "104") (name "/PG5") (class "Default")
      (node (ref "P27") (pin "35") (pinfunction "35_35") (pintype "passive"))
      (node (ref "U16") (pin "90") (pinfunction "PG5/FSMC_A15_90") (pintype "passive"))
    )
    (net (code "105") (name "/PG6") (class "Default")
      (node (ref "P27") (pin "34") (pinfunction "34_34") (pintype "passive"))
      (node (ref "U16") (pin "91") (pinfunction "PG6/FSMC_INT2_91") (pintype "passive"))
    )
    (net (code "106") (name "/PG7") (class "Default")
      (node (ref "P27") (pin "33") (pinfunction "33_33") (pintype "passive"))
      (node (ref "U16") (pin "92") (pinfunction "PG7/FSMC_INT3_92") (pintype "passive"))
    )
    (net (code "107") (name "/PG8") (class "Default")
      (node (ref "P27") (pin "32") (pinfunction "32_32") (pintype "passive"))
      (node (ref "U16") (pin "93") (pinfunction "PG8_93") (pintype "passive"))
    )
    (net (code "108") (name "/PG9") (class "Default")
      (node (ref "P27") (pin "14") (pinfunction "14_14") (pintype "passive"))
      (node (ref "U16") (pin "124") (pinfunction "PG9/FSMC_NE2/FSMC_NCE3_124") (pintype "passive"))
    )
    (net (code "109") (name "/PG10") (class "Default")
      (node (ref "P27") (pin "13") (pinfunction "13_13") (pintype "passive"))
      (node (ref "U16") (pin "125") (pinfunction "PG10/FSMC_NCE4_1/FSMC_NE3_125") (pintype "passive"))
    )
    (net (code "110") (name "/PG11") (class "Default")
      (node (ref "P27") (pin "12") (pinfunction "12_12") (pintype "passive"))
      (node (ref "U16") (pin "126") (pinfunction "PG11/FSMC_NCE4_2_126") (pintype "passive"))
    )
    (net (code "111") (name "/PG12") (class "Default")
      (node (ref "P27") (pin "11") (pinfunction "11_11") (pintype "passive"))
      (node (ref "U16") (pin "127") (pinfunction "PG12/FSMC_NE4_127") (pintype "passive"))
    )
    (net (code "112") (name "/PG13") (class "Default")
      (node (ref "P27") (pin "10") (pinfunction "10_10") (pintype "passive"))
      (node (ref "U16") (pin "128") (pinfunction "PG13/FSMC_A24_128") (pintype "passive"))
    )
    (net (code "113") (name "/PG14") (class "Default")
      (node (ref "P27") (pin "9") (pinfunction "9_9") (pintype "passive"))
      (node (ref "U16") (pin "129") (pinfunction "PG14/FSMC_A25_129") (pintype "passive"))
    )
    (net (code "114") (name "/PG15") (class "Default")
      (node (ref "P27") (pin "8") (pinfunction "8_8") (pintype "passive"))
      (node (ref "U16") (pin "132") (pinfunction "PG15_132") (pintype "passive"))
    )
    (net (code "115") (name "/RESET") (class "Default")
      (node (ref "C93") (pin "1") (pinfunction "1_1") (pintype "passive"))
      (node (ref "D11") (pin "1") (pinfunction "A_1") (pintype "passive"))
      (node (ref "R101") (pin "1") (pinfunction "1_1") (pintype "passive"))
      (node (ref "U16") (pin "25") (pinfunction "NRST_25") (pintype "passive"))
      (node (ref "key3") (pin "1") (pinfunction "1_1") (pintype "passive"))
    )
    (net (code "116") (name "/VDDA") (class "Default")
      (node (ref "C78") (pin "2") (pinfunction "2_2") (pintype "passive"))
      (node (ref "C79") (pin "2") (pinfunction "2_2") (pintype "passive"))
      (node (ref "H10") (pin "2") (pintype "passive"))
      (node (ref "R98") (pin "1") (pinfunction "1_1") (pintype "passive"))
      (node (ref "U16") (pin "33") (pinfunction "VDDA_33") (pintype "passive"))
    )
    (net (code "117") (name "/VREF+") (class "Default")
      (node (ref "C80") (pin "2") (pinfunction "2_2") (pintype "passive"))
      (node (ref "H10") (pin "1") (pintype "passive"))
      (node (ref "U16") (pin "32") (pinfunction "Vref+_32") (pintype "passive"))
    )
    (net (code "118") (name "/WRXD") (class "Default")
      (node (ref "R93") (pin "1") (pinfunction "1_1") (pintype "passive"))
    )
    (net (code "119") (name "/WTXD") (class "Default")
      (node (ref "D10") (pin "1") (pinfunction "A_1") (pintype "passive"))
      (node (ref "LED11") (pin "2") (pinfunction "K_2") (pintype "passive"))
    )
    (net (code "120") (name "ESPVCC2") (class "Default")
      (node (ref "C92") (pin "2") (pinfunction "2_2") (pintype "passive"))
      (node (ref "R99") (pin "1") (pinfunction "1_1") (pintype "passive"))
      (node (ref "U19") (pin "1") (pinfunction "RST_1") (pintype "passive"))
      (node (ref "U19") (pin "8") (pinfunction "VCC_8") (pintype "passive"))
    )
    (net (code "121") (name "Net-(D10-K)") (class "Default")
      (node (ref "D10") (pin "2") (pinfunction "K_2") (pintype "passive"))
      (node (ref "U17") (pin "2") (pinfunction "TXD_2") (pintype "passive"))
    )
    (net (code "122") (name "Net-(D11-K)") (class "Default")
      (node (ref "D11") (pin "2") (pinfunction "K_2") (pintype "passive"))
      (node (ref "Q22") (pin "1") (pinfunction "c_1") (pintype "passive"))
      (node (ref "R92") (pin "1") (pinfunction "1_1") (pintype "passive"))
    )
    (net (code "123") (name "Net-(D12-A)") (class "Default")
      (node (ref "D12") (pin "1") (pinfunction "A_1") (pintype "passive"))
      (node (ref "U18") (pin "1") (pinfunction "VCC_1") (pintype "passive"))
    )
    (net (code "124") (name "Net-(D12-K)") (class "Default")
      (node (ref "D12") (pin "2") (pinfunction "K_2") (pintype "passive"))
      (node (ref "FU4") (pin "2") (pinfunction "2_2") (pintype "passive"))
    )
    (net (code "125") (name "Net-(LED10-K)") (class "Default")
      (node (ref "LED10") (pin "2") (pinfunction "K_2") (pintype "passive"))
      (node (ref "R90") (pin "1") (pinfunction "1_1") (pintype "passive"))
    )
    (net (code "126") (name "Net-(LED11-A)") (class "Default")
      (node (ref "LED11") (pin "1") (pinfunction "A_1") (pintype "passive"))
      (node (ref "R91") (pin "1") (pinfunction "1_1") (pintype "passive"))
    )
    (net (code "127") (name "Net-(P29-Pad3)") (class "Default")
      (node (ref "P29") (pin "3") (pinfunction "3_3") (pintype "passive"))
      (node (ref "R102") (pin "1") (pinfunction "1_1") (pintype "passive"))
    )
    (net (code "128") (name "Net-(P29-Pad4)") (class "Default")
      (node (ref "P29") (pin "4") (pinfunction "4_4") (pintype "passive"))
      (node (ref "R103") (pin "2") (pinfunction "2_2") (pintype "passive"))
    )
    (net (code "129") (name "Net-(Q22-b)") (class "Default")
      (node (ref "Q22") (pin "3") (pinfunction "b_3") (pintype "passive"))
      (node (ref "R94") (pin "2") (pinfunction "2_2") (pintype "passive"))
    )
    (net (code "130") (name "Net-(Q22-e)") (class "Default")
      (node (ref "Q22") (pin "2") (pinfunction "e_2") (pintype "passive"))
      (node (ref "R95") (pin "2") (pinfunction "2_2") (pintype "passive"))
      (node (ref "U17") (pin "14") (pinfunction "RTS#_14") (pintype "passive"))
    )
    (net (code "131") (name "Net-(Q23-b)") (class "Default")
      (node (ref "Q23") (pin "3") (pinfunction "b_3") (pintype "passive"))
      (node (ref "R95") (pin "1") (pinfunction "1_1") (pintype "passive"))
    )
    (net (code "132") (name "Net-(Q23-c)") (class "Default")
      (node (ref "Q23") (pin "1") (pinfunction "c_1") (pintype "passive"))
      (node (ref "R96") (pin "2") (pinfunction "2_2") (pintype "passive"))
    )
    (net (code "133") (name "Net-(U16-OSC_IN)") (class "Default")
      (node (ref "C77") (pin "2") (pinfunction "2_2") (pintype "passive"))
      (node (ref "R97") (pin "2") (pinfunction "2_2") (pintype "passive"))
      (node (ref "U16") (pin "23") (pinfunction "OSC_IN_23") (pintype "passive"))
      (node (ref "XT7") (pin "2") (pinfunction "2_2") (pintype "passive"))
    )
    (net (code "134") (name "Net-(U16-OSC_OUT)") (class "Default")
      (node (ref "2") (pin "2") (pinfunction "2_2") (pintype "passive"))
      (node (ref "R97") (pin "1") (pinfunction "1_1") (pintype "passive"))
      (node (ref "U16") (pin "24") (pinfunction "OSC_OUT_24") (pintype "passive"))
      (node (ref "XT7") (pin "1") (pinfunction "1_1") (pintype "passive"))
    )
    (net (code "135") (name "Net-(U16-VSSA)") (class "Default")
      (node (ref "C78") (pin "1") (pinfunction "1_1") (pintype "passive"))
      (node (ref "C79") (pin "1") (pinfunction "1_1") (pintype "passive"))
      (node (ref "U16") (pin "30") (pinfunction "VSSA_30") (pintype "passive"))
    )
    (net (code "136") (name "Net-(U17-RXD)") (class "Default")
      (node (ref "R93") (pin "2") (pinfunction "2_2") (pintype "passive"))
      (node (ref "U17") (pin "3") (pinfunction "RXD_3") (pintype "passive"))
    )
    (net (code "137") (name "Net-(U17-TDR#)") (class "Default")
      (node (ref "R94") (pin "1") (pinfunction "1_1") (pintype "passive"))
      (node (ref "U17") (pin "13") (pinfunction "TDR#_13") (pintype "passive"))
    )
    (net (code "138") (name "Net-(U17-V3)") (class "Default")
      (node (ref "C71") (pin "1") (pinfunction "1_1") (pintype "passive"))
      (node (ref "U17") (pin "4") (pinfunction "V3_4") (pintype "passive"))
    )
    (net (code "139") (name "Net-(U17-XI)") (class "Default")
      (node (ref "C75") (pin "2") (pinfunction "2_2") (pintype "passive"))
      (node (ref "U17") (pin "7") (pinfunction "XI_7") (pintype "passive"))
      (node (ref "XT6") (pin "1") (pinfunction "1_1") (pintype "passive"))
    )
    (net (code "140") (name "Net-(U17-XO)") (class "Default")
      (node (ref "C76") (pin "2") (pinfunction "2_2") (pintype "passive"))
      (node (ref "U17") (pin "8") (pinfunction "XO_8") (pintype "passive"))
      (node (ref "XT6") (pin "2") (pinfunction "2_2") (pintype "passive"))
    )
    (net (code "141") (name "Net-(U19-EN)") (class "Default")
      (node (ref "R99") (pin "2") (pinfunction "2_2") (pintype "passive"))
      (node (ref "U19") (pin "3") (pinfunction "EN_3") (pintype "passive"))
    )
    (net (code "142") (name "Net-(U19-IO0)") (class "Default")
      (node (ref "H11") (pin "2") (pintype "passive"))
      (node (ref "U19") (pin "18") (pinfunction "IO0_18") (pintype "passive"))
    )
    (net (code "143") (name "Net-(U19-IO15)") (class "Default")
      (node (ref "R100") (pin "2") (pinfunction "2_2") (pintype "passive"))
      (node (ref "U19") (pin "16") (pinfunction "IO15_16") (pintype "passive"))
    )
    (net (code "144") (name "VCC3.3V") (class "Default")
      (node (ref "C74") (pin "1") (pinfunction "1_1") (pintype "passive"))
      (node (ref "C81") (pin "2") (pinfunction "2_2") (pintype "passive"))
      (node (ref "C82") (pin "2") (pinfunction "2_2") (pintype "passive"))
      (node (ref "C83") (pin "2") (pinfunction "2_2") (pintype "passive"))
      (node (ref "C84") (pin "2") (pinfunction "2_2") (pintype "passive"))
      (node (ref "C85") (pin "2") (pinfunction "2_2") (pintype "passive"))
      (node (ref "C86") (pin "2") (pinfunction "2_2") (pintype "passive"))
      (node (ref "C87") (pin "2") (pinfunction "2_2") (pintype "passive"))
      (node (ref "C88") (pin "2") (pinfunction "2_2") (pintype "passive"))
      (node (ref "C89") (pin "2") (pinfunction "2_2") (pintype "passive"))
      (node (ref "C90") (pin "2") (pinfunction "2_2") (pintype "passive"))
      (node (ref "C91") (pin "2") (pinfunction "2_2") (pintype "passive"))
      (node (ref "HTU1") (pin "1") (pinfunction "VCC_1") (pintype "tri_state"))
      (node (ref "LED10") (pin "1") (pinfunction "A_1") (pintype "passive"))
      (node (ref "P29") (pin "1") (pinfunction "1_1") (pintype "passive"))
      (node (ref "P29") (pin "2") (pinfunction "2_2") (pintype "passive"))
      (node (ref "Q23") (pin "2") (pinfunction "e_2") (pintype "passive"))
      (node (ref "R101") (pin "2") (pinfunction "2_2") (pintype "passive"))
      (node (ref "R92") (pin "2") (pinfunction "2_2") (pintype "passive"))
      (node (ref "R98") (pin "2") (pinfunction "2_2") (pintype "passive"))
      (node (ref "U16") (pin "108") (pinfunction "VDD_108") (pintype "passive"))
      (node (ref "U16") (pin "121") (pinfunction "VDD_121") (pintype "passive"))
      (node (ref "U16") (pin "131") (pinfunction "VDD_131") (pintype "passive"))
      (node (ref "U16") (pin "144") (pinfunction "VDD_144") (pintype "passive"))
      (node (ref "U16") (pin "17") (pinfunction "VDD_17") (pintype "passive"))
      (node (ref "U16") (pin "39") (pinfunction "VDD_39") (pintype "passive"))
      (node (ref "U16") (pin "52") (pinfunction "VDD_52") (pintype "passive"))
      (node (ref "U16") (pin "6") (pinfunction "VBAT_6") (pintype "passive"))
      (node (ref "U16") (pin "62") (pinfunction "VDD_62") (pintype "passive"))
      (node (ref "U16") (pin "72") (pinfunction "VDD_72") (pintype "passive"))
      (node (ref "U16") (pin "84") (pinfunction "VDD_84") (pintype "passive"))
      (node (ref "U16") (pin "95") (pinfunction "VDD_95") (pintype "passive"))
    )
    (net (code "145") (name "VCC5V") (class "Default")
      (node (ref "C69") (pin "1") (pinfunction "1_1") (pintype "passive"))
      (node (ref "C70") (pin "1") (pinfunction "1_1") (pintype "passive"))
      (node (ref "FU4") (pin "1") (pinfunction "1_1") (pintype "passive"))
      (node (ref "R91") (pin "2") (pinfunction "2_2") (pintype "passive"))
      (node (ref "U17") (pin "16") (pinfunction "VCC_16") (pintype "passive"))
    )
    (net (code "146") (name "unconnected-(U16-NC-Pad106)") (class "Default")
      (node (ref "U16") (pin "106") (pinfunction "NC_106") (pintype "passive"))
    )
    (net (code "147") (name "unconnected-(U16-PA11{slash}USART1_CTS{slash}CAN_RX{slash}TIM1_CH4{slash}USBDM-Pad103)") (class "Default")
      (node (ref "U16") (pin "103") (pinfunction "PA11/USART1_CTS/CAN_RX/TIM1_CH4/USBDM_103") (pintype "passive"))
    )
    (net (code "148") (name "unconnected-(U17-CTS#-Pad9)") (class "Default")
      (node (ref "U17") (pin "9") (pinfunction "CTS#_9") (pintype "passive"))
    )
    (net (code "149") (name "unconnected-(U17-DCD#-Pad12)") (class "Default")
      (node (ref "U17") (pin "12") (pinfunction "DCD#_12") (pintype "passive"))
    )
    (net (code "150") (name "unconnected-(U17-DSR#-Pad10)") (class "Default")
      (node (ref "U17") (pin "10") (pinfunction "DSR#_10") (pintype "passive"))
    )
    (net (code "151") (name "unconnected-(U17-R232-Pad15)") (class "Default")
      (node (ref "U17") (pin "15") (pinfunction "R232_15") (pintype "passive"))
    )
    (net (code "152") (name "unconnected-(U17-RI#-Pad11)") (class "Default")
      (node (ref "U17") (pin "11") (pinfunction "RI#_11") (pintype "passive"))
    )
    (net (code "153") (name "unconnected-(U19-ADC-Pad2)") (class "Default")
      (node (ref "U19") (pin "2") (pinfunction "ADC_2") (pintype "passive"))
    )
    (net (code "154") (name "unconnected-(U19-C0-Pad9)") (class "Default")
      (node (ref "U19") (pin "9") (pinfunction "C0_9") (pintype "passive"))
    )
    (net (code "155") (name "unconnected-(U19-I9-Pad11)") (class "Default")
      (node (ref "U19") (pin "11") (pinfunction "I9_11") (pintype "passive"))
    )
    (net (code "156") (name "unconnected-(U19-I10-Pad12)") (class "Default")
      (node (ref "U19") (pin "12") (pinfunction "I10_12") (pintype "passive"))
    )
    (net (code "157") (name "unconnected-(U19-IO2-Pad17)") (class "Default")
      (node (ref "U19") (pin "17") (pinfunction "IO2_17") (pintype "passive"))
    )
    (net (code "158") (name "unconnected-(U19-IO4-Pad19)") (class "Default")
      (node (ref "U19") (pin "19") (pinfunction "IO4_19") (pintype "passive"))
    )
    (net (code "159") (name "unconnected-(U19-IO5-Pad20)") (class "Default")
      (node (ref "U19") (pin "20") (pinfunction "IO5_20") (pintype "passive"))
    )
    (net (code "160") (name "unconnected-(U19-IO12-Pad6)") (class "Default")
      (node (ref "U19") (pin "6") (pinfunction "IO12_6") (pintype "passive"))
    )
    (net (code "161") (name "unconnected-(U19-IO13-Pad7)") (class "Default")
      (node (ref "U19") (pin "7") (pinfunction "IO13_7") (pintype "passive"))
    )
    (net (code "162") (name "unconnected-(U19-IO14-Pad5)") (class "Default")
      (node (ref "U19") (pin "5") (pinfunction "IO14_5") (pintype "passive"))
    )
    (net (code "163") (name "unconnected-(U19-IO16-Pad4)") (class "Default")
      (node (ref "U19") (pin "4") (pinfunction "IO16_4") (pintype "passive"))
    )
    (net (code "164") (name "unconnected-(U19-MI-Pad13)") (class "Default")
      (node (ref "U19") (pin "13") (pinfunction "MI_13") (pintype "passive"))
    )
    (net (code "165") (name "unconnected-(U19-MO-Pad10)") (class "Default")
      (node (ref "U19") (pin "10") (pinfunction "MO_10") (pintype "passive"))
    )
    (net (code "166") (name "unconnected-(U19-SK-Pad14)") (class "Default")
      (node (ref "U19") (pin "14") (pinfunction "SK_14") (pintype "passive"))
    )
    (net (code "167") (name "控?") (class "Default")
      (node (ref "2") (pin "1") (pinfunction "1_1") (pintype "passive"))
      (node (ref "C69") (pin "2") (pinfunction "2_2") (pintype "passive"))
      (node (ref "C70") (pin "2") (pinfunction "2_2") (pintype "passive"))
      (node (ref "C71") (pin "2") (pinfunction "2_2") (pintype "passive"))
      (node (ref "C72") (pin "1") (pinfunction "1_1") (pintype "passive"))
      (node (ref "C73") (pin "1") (pinfunction "1_1") (pintype "passive"))
      (node (ref "C74") (pin "2") (pinfunction "2_2") (pintype "passive"))
      (node (ref "C75") (pin "1") (pinfunction "1_1") (pintype "passive"))
      (node (ref "C76") (pin "1") (pinfunction "1_1") (pintype "passive"))
      (node (ref "C77") (pin "1") (pinfunction "1_1") (pintype "passive"))
      (node (ref "C80") (pin "1") (pinfunction "1_1") (pintype "passive"))
      (node (ref "C81") (pin "1") (pinfunction "1_1") (pintype "passive"))
      (node (ref "C82") (pin "1") (pinfunction "1_1") (pintype "passive"))
      (node (ref "C83") (pin "1") (pinfunction "1_1") (pintype "passive"))
      (node (ref "C84") (pin "1") (pinfunction "1_1") (pintype "passive"))
      (node (ref "C85") (pin "1") (pinfunction "1_1") (pintype "passive"))
      (node (ref "C86") (pin "1") (pinfunction "1_1") (pintype "passive"))
      (node (ref "C87") (pin "1") (pinfunction "1_1") (pintype "passive"))
      (node (ref "C88") (pin "1") (pinfunction "1_1") (pintype "passive"))
      (node (ref "C89") (pin "1") (pinfunction "1_1") (pintype "passive"))
      (node (ref "C90") (pin "1") (pinfunction "1_1") (pintype "passive"))
      (node (ref "C91") (pin "1") (pinfunction "1_1") (pintype "passive"))
      (node (ref "C92") (pin "1") (pinfunction "1_1") (pintype "passive"))
      (node (ref "C93") (pin "2") (pinfunction "2_2") (pintype "passive"))
      (node (ref "H11") (pin "1") (pintype "passive"))
      (node (ref "HTU1") (pin "2") (pinfunction "GND_2") (pintype "tri_state"))
      (node (ref "P26") (pin "43") (pinfunction "43_43") (pintype "passive"))
      (node (ref "P27") (pin "44") (pinfunction "44_44") (pintype "passive"))
      (node (ref "P29") (pin "5") (pinfunction "5_5") (pintype "passive"))
      (node (ref "P29") (pin "6") (pinfunction "6_6") (pintype "passive"))
      (node (ref "R100") (pin "1") (pinfunction "1_1") (pintype "passive"))
      (node (ref "U16") (pin "107") (pinfunction "VSS_107") (pintype "passive"))
      (node (ref "U16") (pin "120") (pinfunction "VSS_120") (pintype "passive"))
      (node (ref "U16") (pin "130") (pinfunction "VSS_130") (pintype "passive"))
      (node (ref "U16") (pin "143") (pinfunction "VSS_143") (pintype "passive"))
      (node (ref "U16") (pin "16") (pinfunction "VSS_16") (pintype "passive"))
      (node (ref "U16") (pin "31") (pinfunction "Vref-_31") (pintype "passive"))
      (node (ref "U16") (pin "38") (pinfunction "VSS_38") (pintype "passive"))
      (node (ref "U16") (pin "51") (pinfunction "VSS_51") (pintype "passive"))
      (node (ref "U16") (pin "61") (pinfunction "VSS_61") (pintype "passive"))
      (node (ref "U16") (pin "71") (pinfunction "VSS_71") (pintype "passive"))
      (node (ref "U16") (pin "83") (pinfunction "VSS_83") (pintype "passive"))
      (node (ref "U16") (pin "94") (pinfunction "VSS_94") (pintype "passive"))
      (node (ref "U17") (pin "1") (pinfunction "GND_1") (pintype "passive"))
      (node (ref "U18") (pin "4") (pinfunction "GND_4") (pintype "passive"))
      (node (ref "U18") (pin "5") (pinfunction "5_5") (pintype "tri_state"))
      (node (ref "U18") (pin "6") (pinfunction "6_6") (pintype "tri_state"))
      (node (ref "U19") (pin "15") (pinfunction "GND_15") (pintype "passive"))
      (node (ref "key3") (pin "2") (pinfunction "2_2") (pintype "passive"))
    )
  )
)
